# lcd_helloworld.net
KiCad netlist of a schematic drawn in EAGLE
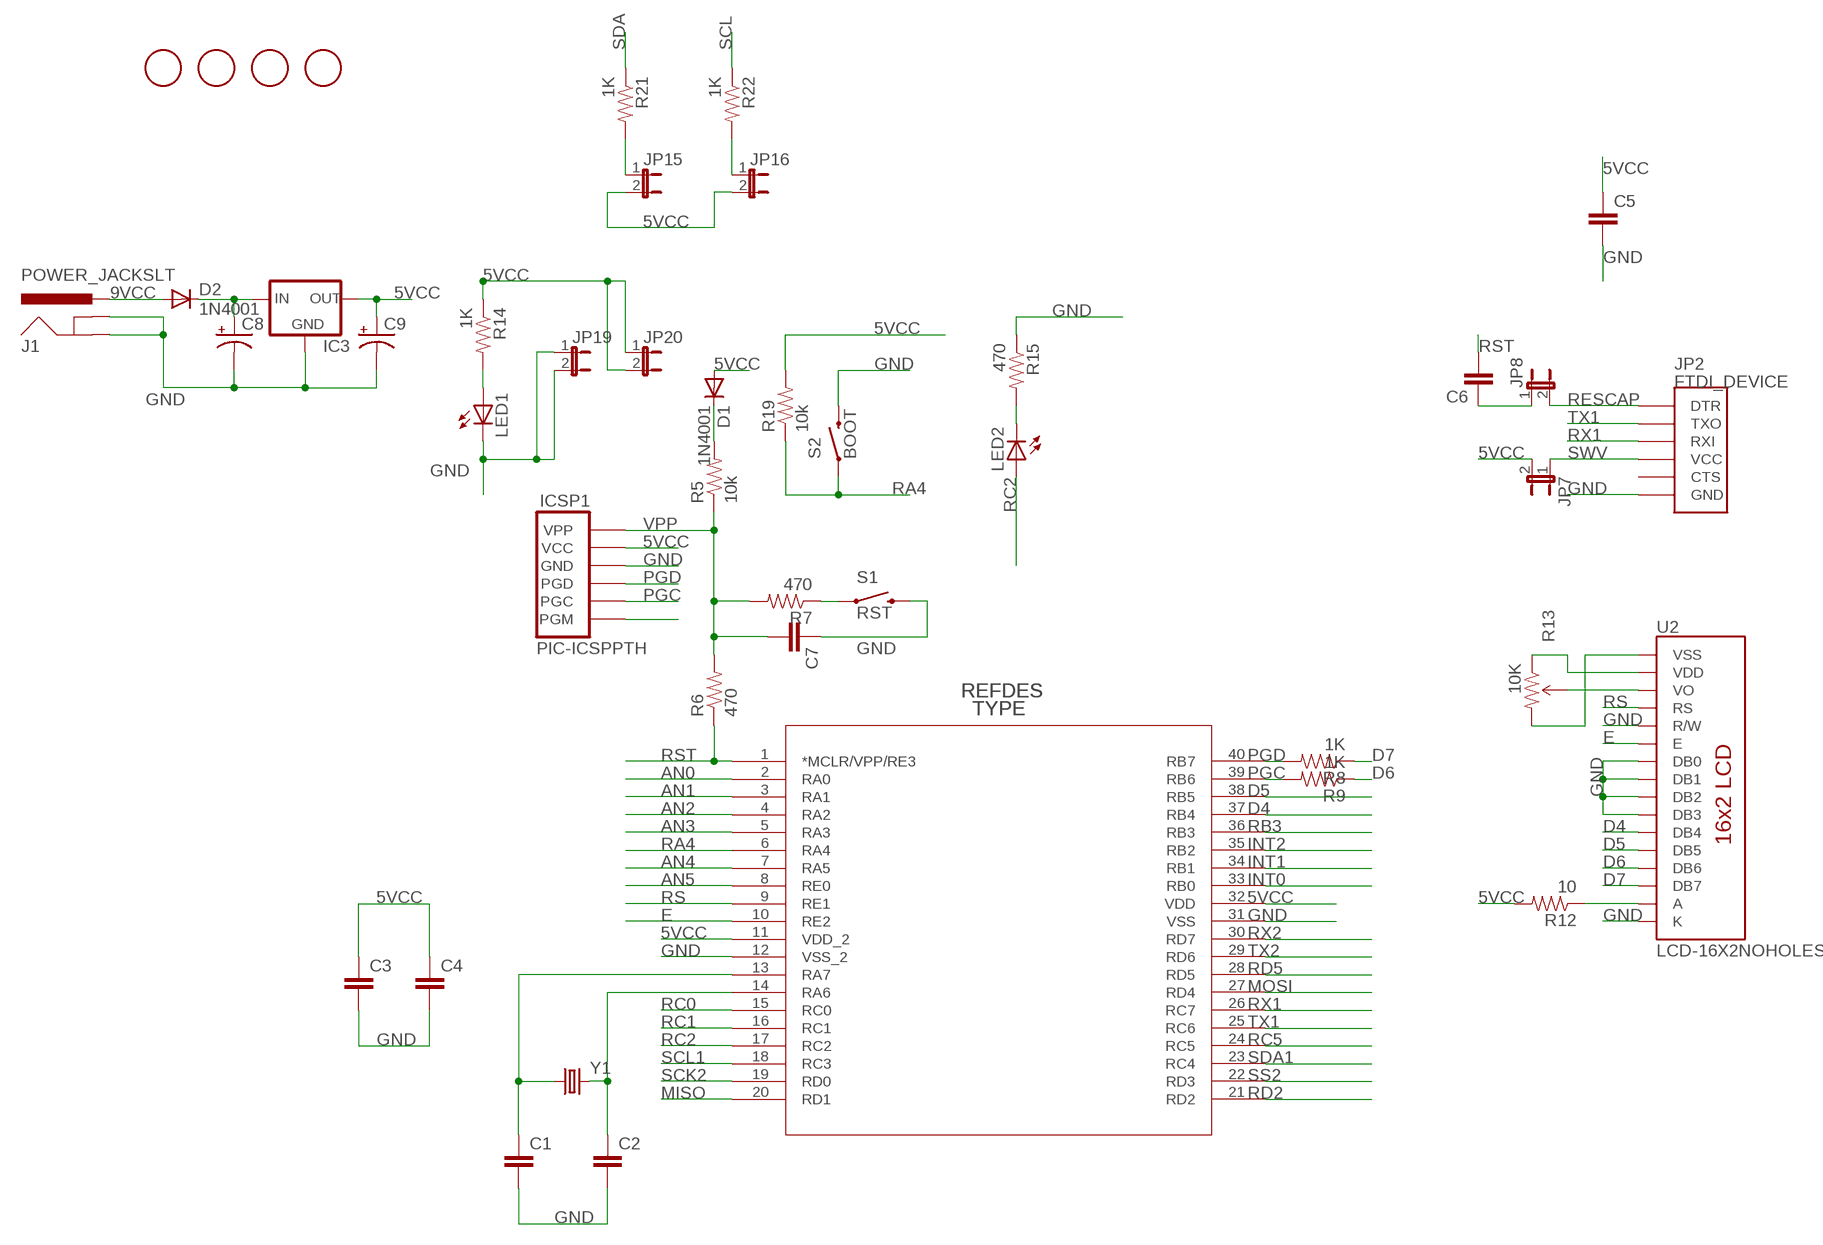
[diagram p0: schematic, sheet 1]

(export (version "E")
  (design (tool "Eeschema 10.0.6"))
  (components
    (comp (ref "C1")
      (value "CAPPTH1")
      (footprint "eagle-import:CAP-PTH-5MM")
      (libsource (lib "eagle-import") (part "CAPPTH1"))
    )
    (comp (ref "C2")
      (value "CAPPTH1")
      (footprint "eagle-import:CAP-PTH-5MM")
      (libsource (lib "eagle-import") (part "CAPPTH1"))
    )
    (comp (ref "C3")
      (value "CAPPTH1")
      (footprint "eagle-import:CAP-PTH-5MM")
      (libsource (lib "eagle-import") (part "CAPPTH1"))
    )
    (comp (ref "C4")
      (value "CAPPTH1")
      (footprint "eagle-import:CAP-PTH-5MM")
      (libsource (lib "eagle-import") (part "CAPPTH1"))
    )
    (comp (ref "C5")
      (value "CAPPTH1")
      (footprint "eagle-import:CAP-PTH-5MM")
      (libsource (lib "eagle-import") (part "CAPPTH1"))
    )
    (comp (ref "C6")
      (value "CAPPTH1")
      (footprint "eagle-import:CAP-PTH-5MM")
      (libsource (lib "eagle-import") (part "CAPPTH1"))
    )
    (comp (ref "C7")
      (value "CAPPTH1")
      (footprint "eagle-import:CAP-PTH-5MM")
      (libsource (lib "eagle-import") (part "CAPPTH1"))
    )
    (comp (ref "C8")
      (value "CAP_POLPTH1")
      (footprint "eagle-import:CPOL-RADIAL-100UF-25V")
      (libsource (lib "eagle-import") (part "CAP_POLPTH1"))
    )
    (comp (ref "C9")
      (value "CAP_POLPTH2")
      (footprint "eagle-import:CPOL-RADIAL-10UF-25V")
      (libsource (lib "eagle-import") (part "CAP_POLPTH2"))
    )
    (comp (ref "D1")
      (value "1N4001")
      (footprint "eagle-import:DIODE-1N4001")
      (libsource (lib "eagle-import") (part "DIODEPTH"))
    )
    (comp (ref "D2")
      (value "1N4001")
      (footprint "eagle-import:DIODE-1N4001")
      (libsource (lib "eagle-import") (part "DIODEPTH"))
    )
    (comp (ref "IC3")
      (value "V_REG_78XXSINK")
      (footprint "eagle-import:TO220-IGO")
      (libsource (lib "eagle-import") (part "V_REG_78XXSINK"))
    )
    (comp (ref "ICSP1")
      (value "PIC-ICSPPTH")
      (footprint "eagle-import:MOLEX-1X6")
      (libsource (lib "eagle-import") (part "PIC-ICSPPTH"))
    )
    (comp (ref "J1")
      (value "POWER_JACKSLT")
      (footprint "eagle-import:POWER_JACK_SLOT")
      (libsource (lib "eagle-import") (part "POWER_JACKSLT"))
    )
    (comp (ref "JP2")
      (value "FTDI_DEVICE")
      (footprint "eagle-import:FTDI_DEVICE_SIDE")
      (libsource (lib "eagle-import") (part "FTDI_DEVICE"))
    )
    (comp (ref "JP7")
      (value "JUMPER-2PTH")
      (footprint "eagle-import:1X02")
      (libsource (lib "eagle-import") (part "JUMPER-2PTH"))
    )
    (comp (ref "JP8")
      (value "JUMPER-2PTH")
      (footprint "eagle-import:1X02")
      (libsource (lib "eagle-import") (part "JUMPER-2PTH"))
    )
    (comp (ref "JP15")
      (value "JUMPER-2PTH")
      (footprint "eagle-import:1X02")
      (libsource (lib "eagle-import") (part "JUMPER-2PTH"))
    )
    (comp (ref "JP16")
      (value "JUMPER-2PTH")
      (footprint "eagle-import:1X02")
      (libsource (lib "eagle-import") (part "JUMPER-2PTH"))
    )
    (comp (ref "JP19")
      (value "JUMPER-2PTH")
      (footprint "eagle-import:1X02")
      (libsource (lib "eagle-import") (part "JUMPER-2PTH"))
    )
    (comp (ref "JP20")
      (value "JUMPER-2PTH")
      (footprint "eagle-import:1X02")
      (libsource (lib "eagle-import") (part "JUMPER-2PTH"))
    )
    (comp (ref "LED1")
      (value "LED3MM")
      (footprint "eagle-import:LED3MM")
      (libsource (lib "eagle-import") (part "LED3MM"))
    )
    (comp (ref "LED2")
      (value "LED3MM")
      (footprint "eagle-import:LED3MM")
      (libsource (lib "eagle-import") (part "LED3MM"))
    )
    (comp (ref "R5")
      (value "10k")
      (footprint "eagle-import:AXIAL-0.3")
      (libsource (lib "eagle-import") (part "SparkFun-Resistors_RESISTORAXIAL-0.3"))
    )
    (comp (ref "R6")
      (value "470")
      (footprint "eagle-import:AXIAL-0.3")
      (libsource (lib "eagle-import") (part "RESISTORAXIAL-0.3"))
    )
    (comp (ref "R7")
      (value "470")
      (footprint "eagle-import:AXIAL-0.3")
      (libsource (lib "eagle-import") (part "RESISTORAXIAL-0.3"))
    )
    (comp (ref "R8")
      (value "1K")
      (footprint "eagle-import:AXIAL-0.3")
      (libsource (lib "eagle-import") (part "RESISTORAXIAL-0.3"))
    )
    (comp (ref "R9")
      (value "1K")
      (footprint "eagle-import:AXIAL-0.3")
      (libsource (lib "eagle-import") (part "RESISTORAXIAL-0.3"))
    )
    (comp (ref "R12")
      (value "10")
      (footprint "eagle-import:AXIAL-0.3")
      (libsource (lib "eagle-import") (part "RESISTORAXIAL-0.3"))
    )
    (comp (ref "R13")
      (value "10K")
      (footprint "eagle-import:TRIM_POT_PTH")
      (libsource (lib "eagle-import") (part "TRIMPOTPTH"))
    )
    (comp (ref "R14")
      (value "1K")
      (footprint "eagle-import:AXIAL-0.3")
      (libsource (lib "eagle-import") (part "RESISTORAXIAL-0.3"))
    )
    (comp (ref "R15")
      (value "470")
      (footprint "eagle-import:AXIAL-0.3")
      (libsource (lib "eagle-import") (part "RESISTORAXIAL-0.3"))
    )
    (comp (ref "R19")
      (value "10k")
      (footprint "eagle-import:AXIAL-0.3")
      (libsource (lib "eagle-import") (part "SparkFun-Resistors_RESISTORAXIAL-0.3"))
    )
    (comp (ref "R21")
      (value "1K")
      (footprint "eagle-import:AXIAL-0.3")
      (libsource (lib "eagle-import") (part "RESISTORAXIAL-0.3"))
    )
    (comp (ref "R22")
      (value "1K")
      (footprint "eagle-import:AXIAL-0.3")
      (libsource (lib "eagle-import") (part "RESISTORAXIAL-0.3"))
    )
    (comp (ref "S1")
      (value "RST")
      (footprint "eagle-import:TACTILE-PTH")
      (libsource (lib "eagle-import") (part "SWITCH-MOMENTARY-2PTH"))
    )
    (comp (ref "S2")
      (value "BOOT")
      (footprint "eagle-import:TACTILE-PTH")
      (libsource (lib "eagle-import") (part "SWITCH-MOMENTARY-2PTH"))
    )
    (comp (ref "U$1")
      (value "MOUNTINGHOLE3.0THIN")
      (footprint "eagle-import:MOUNTINGHOLE_3.0_PLATEDTHIN")
      (libsource (lib "eagle-import") (part "MOUNTINGHOLE3.0THIN"))
    )
    (comp (ref "U$2")
      (value "MOUNTINGHOLE3.0THIN")
      (footprint "eagle-import:MOUNTINGHOLE_3.0_PLATEDTHIN")
      (libsource (lib "eagle-import") (part "MOUNTINGHOLE3.0THIN"))
    )
    (comp (ref "U$3")
      (value "MOUNTINGHOLE3.0THIN")
      (footprint "eagle-import:MOUNTINGHOLE_3.0_PLATEDTHIN")
      (libsource (lib "eagle-import") (part "MOUNTINGHOLE3.0THIN"))
    )
    (comp (ref "U$4")
      (value "MOUNTINGHOLE3.0THIN")
      (footprint "eagle-import:MOUNTINGHOLE_3.0_PLATEDTHIN")
      (libsource (lib "eagle-import") (part "MOUNTINGHOLE3.0THIN"))
    )
    (comp (ref "U1")
      (value "PIC18F46K22")
      (footprint "eagle-import:MICROCHIP_PDIP40_600MC")
      (libsource (lib "eagle-import") (part "MICROCHIP_PIC18F46K22-X_P"))
    )
    (comp (ref "U2")
      (value "LCD-16X2NOHOLES")
      (footprint "eagle-import:LCD-16X2_NOHOLES")
      (libsource (lib "eagle-import") (part "LCD-16X2NOHOLES"))
    )
    (comp (ref "Y1")
      (value "CRYSTALHC49UV")
      (footprint "eagle-import:HC49U-V")
      (libsource (lib "eagle-import") (part "CRYSTALHC49UV"))
    )
  )
  (nets
    (net (code "1") (name "/5VCC") (class "Default")
      (node (ref "C3") (pin "1") (pinfunction "1_1") (pintype "passive"))
      (node (ref "C4") (pin "1") (pinfunction "1_1") (pintype "passive"))
      (node (ref "C5") (pin "1") (pinfunction "1_1") (pintype "passive"))
      (node (ref "C9") (pin "1") (pinfunction "+_1") (pintype "passive"))
      (node (ref "D1") (pin "A") (pinfunction "A_A") (pintype "passive"))
      (node (ref "IC3") (pin "OUT") (pinfunction "OUT_OUT") (pintype "output"))
      (node (ref "ICSP1") (pin "5") (pinfunction "VCC_5") (pintype "bidirectional"))
      (node (ref "JP15") (pin "2") (pinfunction "2_2") (pintype "passive"))
      (node (ref "JP16") (pin "2") (pinfunction "2_2") (pintype "passive"))
      (node (ref "JP20") (pin "1") (pinfunction "1_1") (pintype "passive"))
      (node (ref "JP20") (pin "2") (pinfunction "2_2") (pintype "passive"))
      (node (ref "JP7") (pin "2") (pinfunction "2_2") (pintype "passive"))
      (node (ref "R12") (pin "P$2") (pinfunction "2_P$2") (pintype "passive"))
      (node (ref "R13") (pin "1") (pinfunction "CCW_1") (pintype "passive"))
      (node (ref "R14") (pin "P$1") (pinfunction "1_P$1") (pintype "passive"))
      (node (ref "R19") (pin "P$2") (pinfunction "2_P$2") (pintype "passive"))
      (node (ref "U1") (pin "11") (pinfunction "VDD_2_11") (pintype "passive"))
      (node (ref "U1") (pin "32") (pinfunction "VDD_32") (pintype "passive"))
      (node (ref "U2") (pin "2") (pinfunction "VDD_2") (pintype "power_in"))
    )
    (net (code "2") (name "/9VCC") (class "Default")
      (node (ref "D2") (pin "A") (pinfunction "A_A") (pintype "passive"))
      (node (ref "J1") (pin "PWR") (pinfunction "PWR_PWR") (pintype "bidirectional"))
    )
    (net (code "3") (name "/AN0") (class "Default")
      (node (ref "U1") (pin "2") (pinfunction "RA0_2") (pintype "passive"))
    )
    (net (code "4") (name "/AN1") (class "Default")
      (node (ref "U1") (pin "3") (pinfunction "RA1_3") (pintype "passive"))
    )
    (net (code "5") (name "/AN2") (class "Default")
      (node (ref "U1") (pin "4") (pinfunction "RA2_4") (pintype "passive"))
    )
    (net (code "6") (name "/AN3") (class "Default")
      (node (ref "U1") (pin "5") (pinfunction "RA3_5") (pintype "passive"))
    )
    (net (code "7") (name "/AN4") (class "Default")
      (node (ref "U1") (pin "7") (pinfunction "RA5_7") (pintype "passive"))
    )
    (net (code "8") (name "/AN5") (class "Default")
      (node (ref "U1") (pin "8") (pinfunction "RE0_8") (pintype "passive"))
    )
    (net (code "9") (name "/D4") (class "Default")
      (node (ref "U1") (pin "37") (pinfunction "RB4_37") (pintype "passive"))
      (node (ref "U2") (pin "11") (pinfunction "DB4_11") (pintype "bidirectional"))
    )
    (net (code "10") (name "/D5") (class "Default")
      (node (ref "U1") (pin "38") (pinfunction "RB5_38") (pintype "passive"))
      (node (ref "U2") (pin "12") (pinfunction "DB5_12") (pintype "bidirectional"))
    )
    (net (code "11") (name "/D6") (class "Default")
      (node (ref "R9") (pin "P$1") (pinfunction "1_P$1") (pintype "passive"))
      (node (ref "U2") (pin "13") (pinfunction "DB6_13") (pintype "bidirectional"))
    )
    (net (code "12") (name "/D7") (class "Default")
      (node (ref "R8") (pin "P$1") (pinfunction "1_P$1") (pintype "passive"))
      (node (ref "U2") (pin "14") (pinfunction "DB7_14") (pintype "bidirectional"))
    )
    (net (code "13") (name "/E") (class "Default")
      (node (ref "U1") (pin "10") (pinfunction "RE2_10") (pintype "passive"))
      (node (ref "U2") (pin "6") (pinfunction "E_6") (pintype "input"))
    )
    (net (code "14") (name "/GND") (class "Default")
      (node (ref "C1") (pin "2") (pinfunction "2_2") (pintype "passive"))
      (node (ref "C2") (pin "2") (pinfunction "2_2") (pintype "passive"))
      (node (ref "C3") (pin "2") (pinfunction "2_2") (pintype "passive"))
      (node (ref "C4") (pin "2") (pinfunction "2_2") (pintype "passive"))
      (node (ref "C5") (pin "2") (pinfunction "2_2") (pintype "passive"))
      (node (ref "C7") (pin "1") (pinfunction "1_1") (pintype "passive"))
      (node (ref "C8") (pin "2") (pinfunction "-_2") (pintype "passive"))
      (node (ref "C9") (pin "2") (pinfunction "-_2") (pintype "passive"))
      (node (ref "IC3") (pin "GND") (pinfunction "GND_GND") (pintype "input"))
      (node (ref "ICSP1") (pin "4") (pinfunction "GND_4") (pintype "bidirectional"))
      (node (ref "J1") (pin "GND@1") (pinfunction "GNDBREAK_GND@1") (pintype "bidirectional"))
      (node (ref "J1") (pin "GND@2") (pinfunction "GND_GND@2") (pintype "bidirectional"))
      (node (ref "JP19") (pin "1") (pinfunction "1_1") (pintype "passive"))
      (node (ref "JP19") (pin "2") (pinfunction "2_2") (pintype "passive"))
      (node (ref "JP2") (pin "P$6") (pinfunction "GND_P$6") (pintype "bidirectional"))
      (node (ref "LED1") (pin "K") (pinfunction "C_K") (pintype "passive"))
      (node (ref "R13") (pin "3") (pinfunction "CW_3") (pintype "passive"))
      (node (ref "R15") (pin "P$1") (pinfunction "1_P$1") (pintype "passive"))
      (node (ref "S1") (pin "3") (pinfunction "2_3") (pintype "passive"))
      (node (ref "S2") (pin "3") (pinfunction "2_3") (pintype "passive"))
      (node (ref "U1") (pin "12") (pinfunction "VSS_2_12") (pintype "passive"))
      (node (ref "U1") (pin "31") (pinfunction "VSS_31") (pintype "passive"))
      (node (ref "U2") (pin "1") (pinfunction "VSS_1") (pintype "power_in"))
      (node (ref "U2") (pin "10") (pinfunction "DB3_10") (pintype "bidirectional"))
      (node (ref "U2") (pin "16") (pinfunction "K_16") (pintype "power_in"))
      (node (ref "U2") (pin "5") (pinfunction "R/W_5") (pintype "input"))
      (node (ref "U2") (pin "7") (pinfunction "DB0_7") (pintype "bidirectional"))
      (node (ref "U2") (pin "8") (pinfunction "DB1_8") (pintype "bidirectional"))
      (node (ref "U2") (pin "9") (pinfunction "DB2_9") (pintype "bidirectional"))
    )
    (net (code "15") (name "/INT0") (class "Default")
      (node (ref "U1") (pin "33") (pinfunction "RB0_33") (pintype "passive"))
    )
    (net (code "16") (name "/INT1") (class "Default")
      (node (ref "U1") (pin "34") (pinfunction "RB1_34") (pintype "passive"))
    )
    (net (code "17") (name "/INT2") (class "Default")
      (node (ref "U1") (pin "35") (pinfunction "RB2_35") (pintype "passive"))
    )
    (net (code "18") (name "/MISO") (class "Default")
      (node (ref "U1") (pin "20") (pinfunction "RD1_20") (pintype "passive"))
    )
    (net (code "19") (name "/MOSI") (class "Default")
      (node (ref "U1") (pin "27") (pinfunction "RD4_27") (pintype "passive"))
    )
    (net (code "20") (name "/PGC") (class "Default")
      (node (ref "ICSP1") (pin "2") (pinfunction "PGC_2") (pintype "bidirectional"))
      (node (ref "R9") (pin "P$2") (pinfunction "2_P$2") (pintype "passive"))
      (node (ref "U1") (pin "39") (pinfunction "RB6_39") (pintype "passive"))
    )
    (net (code "21") (name "/PGD") (class "Default")
      (node (ref "ICSP1") (pin "3") (pinfunction "PGD_3") (pintype "bidirectional"))
      (node (ref "R8") (pin "P$2") (pinfunction "2_P$2") (pintype "passive"))
      (node (ref "U1") (pin "40") (pinfunction "RB7_40") (pintype "passive"))
    )
    (net (code "22") (name "/RA4") (class "Default")
      (node (ref "R19") (pin "P$1") (pinfunction "1_P$1") (pintype "passive"))
      (node (ref "S2") (pin "1") (pinfunction "1_1") (pintype "passive"))
      (node (ref "U1") (pin "6") (pinfunction "RA4_6") (pintype "passive"))
    )
    (net (code "23") (name "/RB3") (class "Default")
      (node (ref "U1") (pin "36") (pinfunction "RB3_36") (pintype "passive"))
    )
    (net (code "24") (name "/RC0") (class "Default")
      (node (ref "U1") (pin "15") (pinfunction "RC0_15") (pintype "passive"))
    )
    (net (code "25") (name "/RC1") (class "Default")
      (node (ref "U1") (pin "16") (pinfunction "RC1_16") (pintype "passive"))
    )
    (net (code "26") (name "/RC2") (class "Default")
      (node (ref "LED2") (pin "A") (pinfunction "A_A") (pintype "passive"))
      (node (ref "U1") (pin "17") (pinfunction "RC2_17") (pintype "passive"))
    )
    (net (code "27") (name "/RC5") (class "Default")
      (node (ref "U1") (pin "24") (pinfunction "RC5_24") (pintype "passive"))
    )
    (net (code "28") (name "/RD2") (class "Default")
      (node (ref "U1") (pin "21") (pinfunction "RD2_21") (pintype "passive"))
    )
    (net (code "29") (name "/RD5") (class "Default")
      (node (ref "U1") (pin "28") (pinfunction "RD5_28") (pintype "passive"))
    )
    (net (code "30") (name "/RESCAP") (class "Default")
      (node (ref "JP2") (pin "P$1") (pinfunction "DTR_P$1") (pintype "bidirectional"))
      (node (ref "JP8") (pin "2") (pinfunction "2_2") (pintype "passive"))
    )
    (net (code "31") (name "/RS") (class "Default")
      (node (ref "U1") (pin "9") (pinfunction "RE1_9") (pintype "passive"))
      (node (ref "U2") (pin "4") (pinfunction "RS_4") (pintype "input"))
    )
    (net (code "32") (name "/RST") (class "Default")
      (node (ref "C6") (pin "2") (pinfunction "2_2") (pintype "passive"))
      (node (ref "R6") (pin "P$1") (pinfunction "1_P$1") (pintype "passive"))
      (node (ref "U1") (pin "1") (pinfunction "*MCLR/VPP/RE3_1") (pintype "passive"))
    )
    (net (code "33") (name "/RX1") (class "Default")
      (node (ref "JP2") (pin "P$3") (pinfunction "RXI_P$3") (pintype "bidirectional"))
      (node (ref "U1") (pin "26") (pinfunction "RC7_26") (pintype "passive"))
    )
    (net (code "34") (name "/RX2") (class "Default")
      (node (ref "U1") (pin "30") (pinfunction "RD7_30") (pintype "passive"))
    )
    (net (code "35") (name "/SCK2") (class "Default")
      (node (ref "U1") (pin "19") (pinfunction "RD0_19") (pintype "passive"))
    )
    (net (code "36") (name "/SCL") (class "Default")
      (node (ref "R22") (pin "P$1") (pinfunction "1_P$1") (pintype "passive"))
    )
    (net (code "37") (name "/SCL1") (class "Default")
      (node (ref "U1") (pin "18") (pinfunction "RC3_18") (pintype "passive"))
    )
    (net (code "38") (name "/SDA") (class "Default")
      (node (ref "R21") (pin "P$1") (pinfunction "1_P$1") (pintype "passive"))
    )
    (net (code "39") (name "/SDA1") (class "Default")
      (node (ref "U1") (pin "23") (pinfunction "RC4_23") (pintype "passive"))
    )
    (net (code "40") (name "/SS2") (class "Default")
      (node (ref "U1") (pin "22") (pinfunction "RD3_22") (pintype "passive"))
    )
    (net (code "41") (name "/SWV") (class "Default")
      (node (ref "JP2") (pin "P$4") (pinfunction "VCC_P$4") (pintype "bidirectional"))
      (node (ref "JP7") (pin "1") (pinfunction "1_1") (pintype "passive"))
    )
    (net (code "42") (name "/TX1") (class "Default")
      (node (ref "JP2") (pin "P$2") (pinfunction "TXO_P$2") (pintype "bidirectional"))
      (node (ref "U1") (pin "25") (pinfunction "RC6_25") (pintype "passive"))
    )
    (net (code "43") (name "/TX2") (class "Default")
      (node (ref "U1") (pin "29") (pinfunction "RD6_29") (pintype "passive"))
    )
    (net (code "44") (name "/VPP") (class "Default")
      (node (ref "C7") (pin "2") (pinfunction "2_2") (pintype "passive"))
      (node (ref "ICSP1") (pin "6") (pinfunction "VPP_6") (pintype "bidirectional"))
      (node (ref "R5") (pin "P$1") (pinfunction "1_P$1") (pintype "passive"))
      (node (ref "R6") (pin "P$2") (pinfunction "2_P$2") (pintype "passive"))
      (node (ref "R7") (pin "P$2") (pinfunction "2_P$2") (pintype "passive"))
    )
    (net (code "45") (name "Net-(C6-Pad1)") (class "Default")
      (node (ref "C6") (pin "1") (pinfunction "1_1") (pintype "passive"))
      (node (ref "JP8") (pin "1") (pinfunction "1_1") (pintype "passive"))
    )
    (net (code "46") (name "Net-(C8-+)") (class "Default")
      (node (ref "C8") (pin "1") (pinfunction "+_1") (pintype "passive"))
      (node (ref "D2") (pin "C") (pinfunction "C_C") (pintype "passive"))
      (node (ref "IC3") (pin "IN") (pinfunction "IN_IN") (pintype "input"))
    )
    (net (code "47") (name "Net-(LED2-C)") (class "Default")
      (node (ref "LED2") (pin "K") (pinfunction "C_K") (pintype "passive"))
      (node (ref "R15") (pin "P$2") (pinfunction "2_P$2") (pintype "passive"))
    )
    (net (code "48") (name "Net-(R5-2)") (class "Default")
      (node (ref "D1") (pin "C") (pinfunction "C_C") (pintype "passive"))
      (node (ref "R5") (pin "P$2") (pinfunction "2_P$2") (pintype "passive"))
    )
    (net (code "49") (name "Net-(R7-1)") (class "Default")
      (node (ref "R7") (pin "P$1") (pinfunction "1_P$1") (pintype "passive"))
      (node (ref "S1") (pin "1") (pinfunction "1_1") (pintype "passive"))
    )
    (net (code "50") (name "Net-(R12-1)") (class "Default")
      (node (ref "R12") (pin "P$1") (pinfunction "1_P$1") (pintype "passive"))
      (node (ref "U2") (pin "15") (pinfunction "A_15") (pintype "power_in"))
    )
    (net (code "51") (name "Net-(R13-WIPER)") (class "Default")
      (node (ref "R13") (pin "2") (pinfunction "WIPER_2") (pintype "passive"))
      (node (ref "U2") (pin "3") (pinfunction "VO_3") (pintype "bidirectional"))
    )
    (net (code "52") (name "Net-(R14-2)") (class "Default")
      (node (ref "LED1") (pin "A") (pinfunction "A_A") (pintype "passive"))
      (node (ref "R14") (pin "P$2") (pinfunction "2_P$2") (pintype "passive"))
    )
    (net (code "53") (name "Net-(R21-2)") (class "Default")
      (node (ref "JP15") (pin "1") (pinfunction "1_1") (pintype "passive"))
      (node (ref "R21") (pin "P$2") (pinfunction "2_P$2") (pintype "passive"))
    )
    (net (code "54") (name "Net-(R22-2)") (class "Default")
      (node (ref "JP16") (pin "1") (pinfunction "1_1") (pintype "passive"))
      (node (ref "R22") (pin "P$2") (pinfunction "2_P$2") (pintype "passive"))
    )
    (net (code "55") (name "Net-(U1-RA6)") (class "Default")
      (node (ref "C2") (pin "1") (pinfunction "1_1") (pintype "passive"))
      (node (ref "U1") (pin "14") (pinfunction "RA6_14") (pintype "passive"))
      (node (ref "Y1") (pin "2") (pinfunction "2_2") (pintype "passive"))
    )
    (net (code "56") (name "Net-(U1-RA7)") (class "Default")
      (node (ref "C1") (pin "1") (pinfunction "1_1") (pintype "passive"))
      (node (ref "U1") (pin "13") (pinfunction "RA7_13") (pintype "passive"))
      (node (ref "Y1") (pin "1") (pinfunction "1_1") (pintype "passive"))
    )
    (net (code "57") (name "unconnected-(ICSP1-PGM-Pad1)") (class "Default")
      (node (ref "ICSP1") (pin "1") (pinfunction "PGM_1") (pintype "bidirectional"))
    )
    (net (code "58") (name "unconnected-(JP2-CTS-PadP$5)") (class "Default")
      (node (ref "JP2") (pin "P$5") (pinfunction "CTS_P$5") (pintype "bidirectional"))
    )
  )
)
